# PhoneRobot.net
KiCad netlist of a schematic drawn in EAGLE
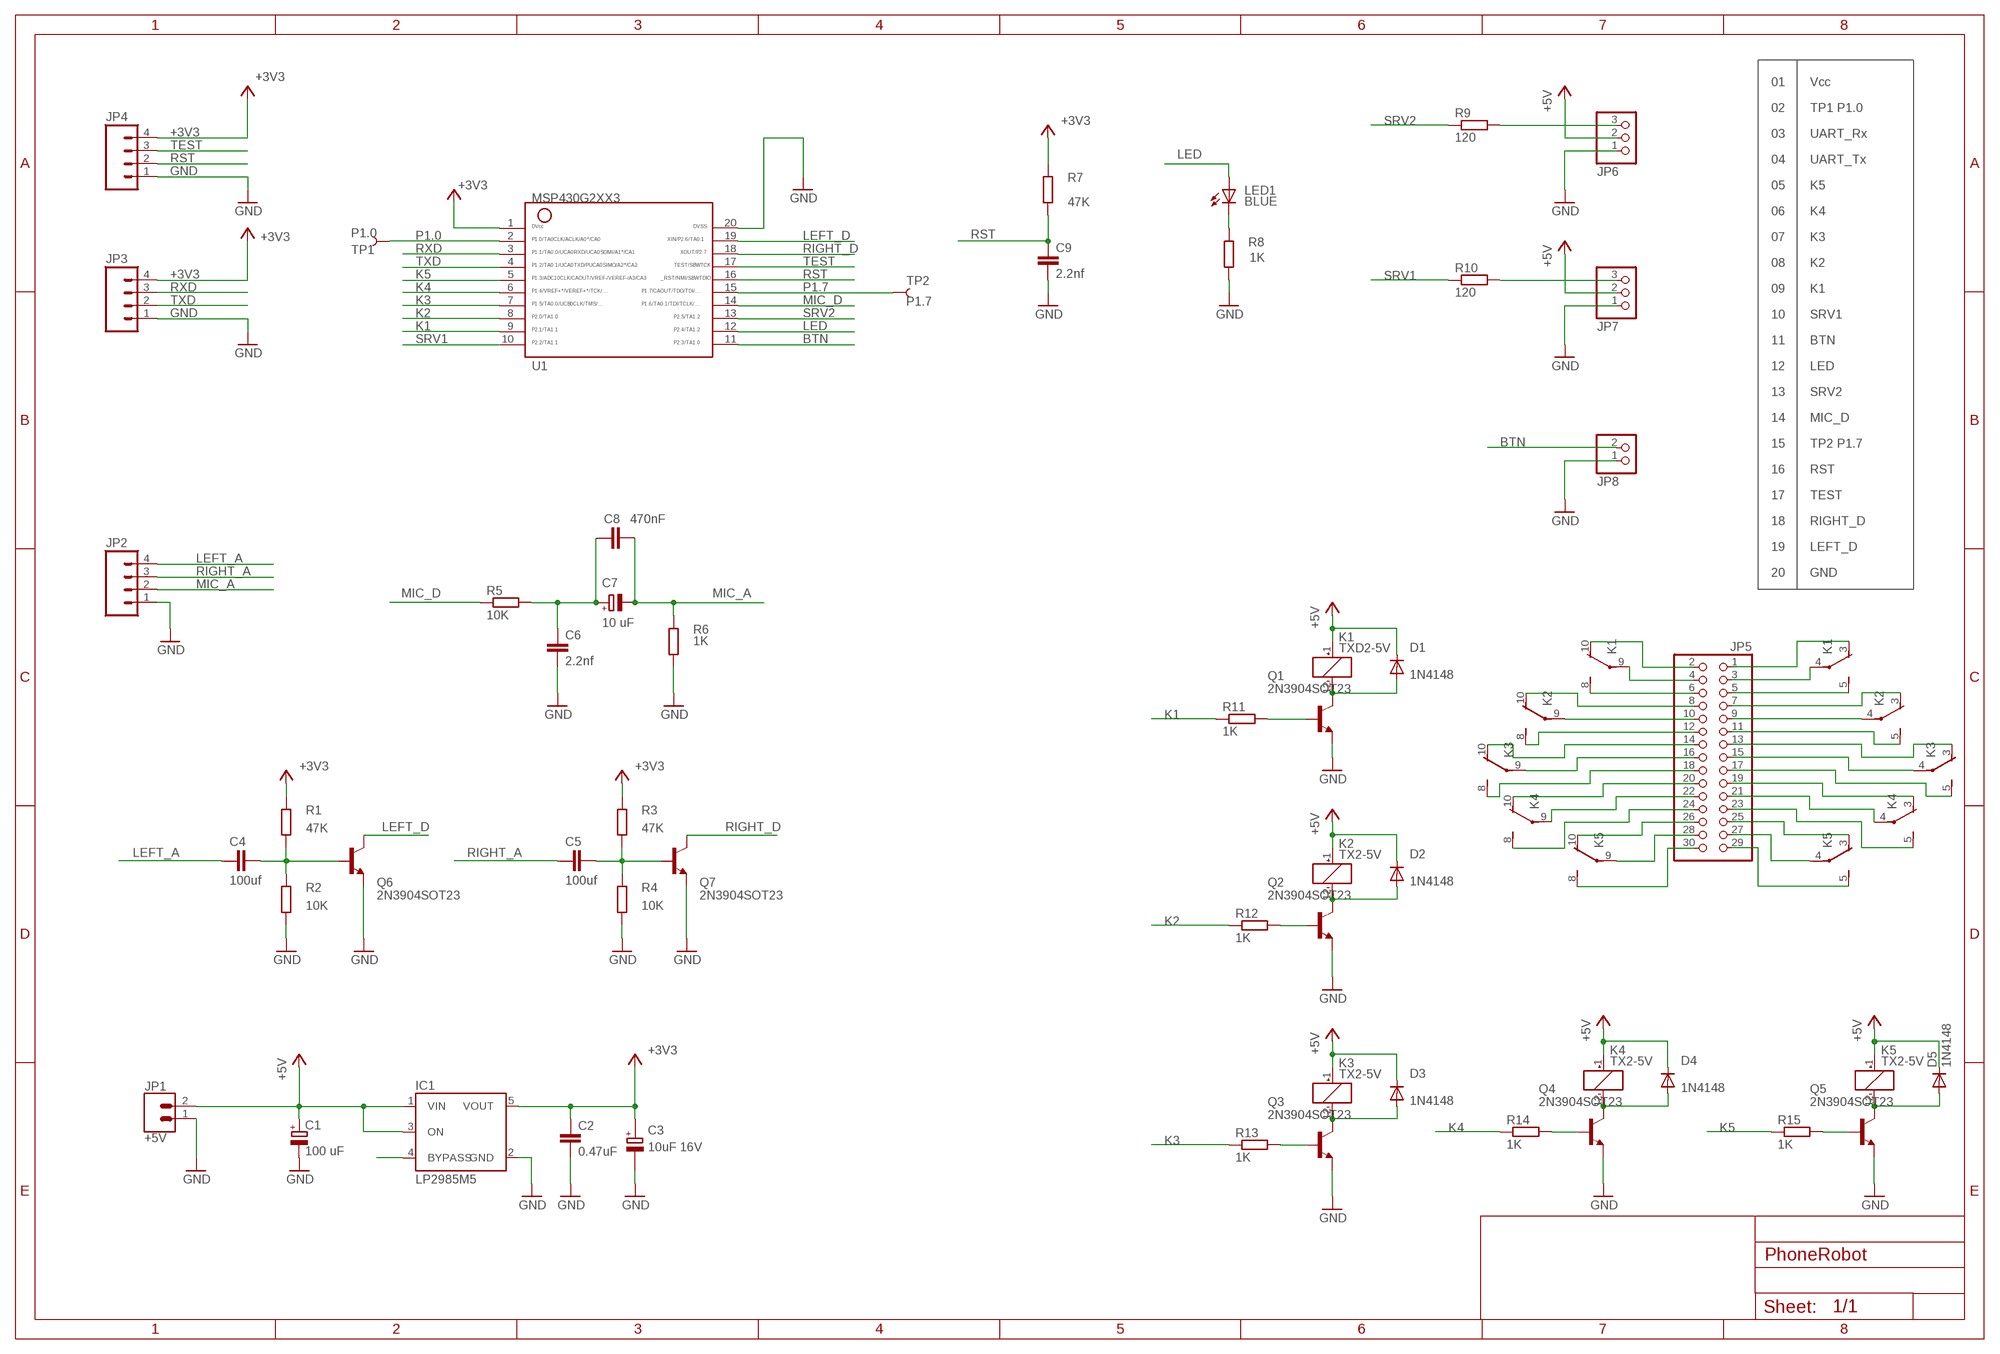
[diagram p0: schematic, sheet 1]

(export (version "E")
  (design (tool "Eeschema 10.0.6"))
  (components
    (comp (ref "C1")
      (value "100 uF")
      (footprint "eagle-import:E2,5-7")
      (libsource (lib "eagle-import") (part "CPOL-EUE2.5-7"))
    )
    (comp (ref "C2")
      (value "0.47uF")
      (footprint "eagle-import:C0805")
      (libsource (lib "eagle-import") (part "C-EUC0805"))
    )
    (comp (ref "C3")
      (value "10uF 16V")
      (footprint "eagle-import:CAPMP3216X180N")
      (libsource (lib "eagle-import") (part "POLARISED_A_CASE"))
    )
    (comp (ref "C4")
      (value "100uf")
      (footprint "eagle-import:C0805")
      (libsource (lib "eagle-import") (part "C-EUC0805"))
    )
    (comp (ref "C5")
      (value "100uf")
      (footprint "eagle-import:C0805")
      (libsource (lib "eagle-import") (part "C-EUC0805"))
    )
    (comp (ref "C6")
      (value "2.2nf")
      (footprint "eagle-import:C0805")
      (libsource (lib "eagle-import") (part "C-EUC0805"))
    )
    (comp (ref "C7")
      (value "10 uF")
      (footprint "eagle-import:E2,5-7")
      (libsource (lib "eagle-import") (part "CPOL-EUE2.5-7"))
    )
    (comp (ref "C8")
      (value "470nF")
      (footprint "eagle-import:C0805")
      (libsource (lib "eagle-import") (part "C-EUC0805"))
    )
    (comp (ref "C9")
      (value "2.2nf")
      (footprint "eagle-import:C0805")
      (libsource (lib "eagle-import") (part "C-EUC0805"))
    )
    (comp (ref "D1")
      (value "1N4148")
      (footprint "eagle-import:SOD123")
      (libsource (lib "eagle-import") (part "DIODE-SOD123"))
    )
    (comp (ref "D2")
      (value "1N4148")
      (footprint "eagle-import:SOD123")
      (libsource (lib "eagle-import") (part "DIODE-SOD123"))
    )
    (comp (ref "D3")
      (value "1N4148")
      (footprint "eagle-import:SOD123")
      (libsource (lib "eagle-import") (part "DIODE-SOD123"))
    )
    (comp (ref "D4")
      (value "1N4148")
      (footprint "eagle-import:SOD123")
      (libsource (lib "eagle-import") (part "DIODE-SOD123"))
    )
    (comp (ref "D5")
      (value "1N4148")
      (footprint "eagle-import:SOD123")
      (libsource (lib "eagle-import") (part "DIODE-SOD123"))
    )
    (comp (ref "IC1")
      (value "LP2985M5")
      (footprint "eagle-import:SOT23-5")
      (libsource (lib "eagle-import") (part "LP2985M5"))
    )
    (comp (ref "JP1")
      (value "+5V")
      (footprint "eagle-import:BLUE_TERM")
      (libsource (lib "eagle-import") (part "BLUE_TERM"))
    )
    (comp (ref "JP2")
      (value "M04PTH")
      (footprint "eagle-import:1X04")
      (libsource (lib "eagle-import") (part "M04PTH"))
    )
    (comp (ref "JP3")
      (value "M04PTH")
      (footprint "eagle-import:1X04")
      (libsource (lib "eagle-import") (part "M04PTH"))
    )
    (comp (ref "JP4")
      (value "M04PTH")
      (footprint "eagle-import:1X04")
      (libsource (lib "eagle-import") (part "M04PTH"))
    )
    (comp (ref "JP5")
      (value "PINHD-2X15")
      (footprint "eagle-import:2X15")
      (libsource (lib "eagle-import") (part "PINHD-2X15"))
    )
    (comp (ref "JP6")
      (value "PINHD-1X3")
      (footprint "eagle-import:1X03")
      (libsource (lib "eagle-import") (part "PINHD-1X3"))
    )
    (comp (ref "JP7")
      (value "PINHD-1X3")
      (footprint "eagle-import:1X03")
      (libsource (lib "eagle-import") (part "PINHD-1X3"))
    )
    (comp (ref "JP8")
      (value "PINHD-1X2")
      (footprint "eagle-import:1X02")
      (libsource (lib "eagle-import") (part "PINHD-1X2"))
    )
    (comp (ref "K1")
      (value "TXD2-5V")
      (footprint "eagle-import:TXD2")
      (libsource (lib "eagle-import") (part "TX?-D25V"))
    )
    (comp (ref "K2")
      (value "TX2-5V")
      (footprint "eagle-import:TX2")
      (fields (field (name "MF") "AROMAT/ MATSUSHITA"))
      (libsource (lib "eagle-import") (part "TX2?-5V"))
    )
    (comp (ref "K3")
      (value "TX2-5V")
      (footprint "eagle-import:TX2")
      (fields (field (name "MF") "AROMAT/ MATSUSHITA"))
      (libsource (lib "eagle-import") (part "TX2?-5V"))
    )
    (comp (ref "K4")
      (value "TX2-5V")
      (footprint "eagle-import:TX2")
      (fields (field (name "MF") "AROMAT/ MATSUSHITA"))
      (libsource (lib "eagle-import") (part "TX2?-5V"))
    )
    (comp (ref "K5")
      (value "TX2-5V")
      (footprint "eagle-import:TX2")
      (fields (field (name "MF") "AROMAT/ MATSUSHITA"))
      (libsource (lib "eagle-import") (part "TX2?-5V"))
    )
    (comp (ref "LED1")
      (value "BLUE")
      (footprint "eagle-import:CHIP-LED0805")
      (libsource (lib "eagle-import") (part "LEDCHIP-LED0805"))
    )
    (comp (ref "Q1")
      (value "2N3904SOT23")
      (footprint "eagle-import:SOT23-BEC")
      (libsource (lib "eagle-import") (part "2N3904SOT23"))
    )
    (comp (ref "Q2")
      (value "2N3904SOT23")
      (footprint "eagle-import:SOT23-BEC")
      (libsource (lib "eagle-import") (part "2N3904SOT23"))
    )
    (comp (ref "Q3")
      (value "2N3904SOT23")
      (footprint "eagle-import:SOT23-BEC")
      (libsource (lib "eagle-import") (part "2N3904SOT23"))
    )
    (comp (ref "Q4")
      (value "2N3904SOT23")
      (footprint "eagle-import:SOT23-BEC")
      (libsource (lib "eagle-import") (part "2N3904SOT23"))
    )
    (comp (ref "Q5")
      (value "2N3904SOT23")
      (footprint "eagle-import:SOT23-BEC")
      (libsource (lib "eagle-import") (part "2N3904SOT23"))
    )
    (comp (ref "Q6")
      (value "2N3904SOT23")
      (footprint "eagle-import:SOT23-BEC")
      (libsource (lib "eagle-import") (part "2N3904SOT23"))
    )
    (comp (ref "Q7")
      (value "2N3904SOT23")
      (footprint "eagle-import:SOT23-BEC")
      (libsource (lib "eagle-import") (part "2N3904SOT23"))
    )
    (comp (ref "R1")
      (value "47K")
      (footprint "eagle-import:R0805")
      (libsource (lib "eagle-import") (part "R-EU_R0805"))
    )
    (comp (ref "R2")
      (value "10K")
      (footprint "eagle-import:R0805")
      (libsource (lib "eagle-import") (part "R-EU_R0805"))
    )
    (comp (ref "R3")
      (value "47K")
      (footprint "eagle-import:R0805")
      (libsource (lib "eagle-import") (part "R-EU_R0805"))
    )
    (comp (ref "R4")
      (value "10K")
      (footprint "eagle-import:R0805")
      (libsource (lib "eagle-import") (part "R-EU_R0805"))
    )
    (comp (ref "R5")
      (value "10K")
      (footprint "eagle-import:R0805")
      (libsource (lib "eagle-import") (part "R-EU_R0805"))
    )
    (comp (ref "R6")
      (value "1K")
      (footprint "eagle-import:R0805")
      (libsource (lib "eagle-import") (part "R-EU_R0805"))
    )
    (comp (ref "R7")
      (value "47K")
      (footprint "eagle-import:R0805")
      (libsource (lib "eagle-import") (part "R-EU_R0805"))
    )
    (comp (ref "R8")
      (value "1K")
      (footprint "eagle-import:R0805")
      (libsource (lib "eagle-import") (part "R-EU_R0805"))
    )
    (comp (ref "R9")
      (value "120")
      (footprint "eagle-import:R0805")
      (libsource (lib "eagle-import") (part "R-EU_R0805"))
    )
    (comp (ref "R10")
      (value "120")
      (footprint "eagle-import:R0805")
      (libsource (lib "eagle-import") (part "R-EU_R0805"))
    )
    (comp (ref "R11")
      (value "1K")
      (footprint "eagle-import:R0805")
      (libsource (lib "eagle-import") (part "R-EU_R0805"))
    )
    (comp (ref "R12")
      (value "1K")
      (footprint "eagle-import:R0805")
      (libsource (lib "eagle-import") (part "R-EU_R0805"))
    )
    (comp (ref "R13")
      (value "1K")
      (footprint "eagle-import:R0805")
      (libsource (lib "eagle-import") (part "R-EU_R0805"))
    )
    (comp (ref "R14")
      (value "1K")
      (footprint "eagle-import:R0805")
      (libsource (lib "eagle-import") (part "R-EU_R0805"))
    )
    (comp (ref "R15")
      (value "1K")
      (footprint "eagle-import:R0805")
      (libsource (lib "eagle-import") (part "R-EU_R0805"))
    )
    (comp (ref "TP1")
      (value "P1.0")
      (footprint "eagle-import:PAD.03X.03")
      (libsource (lib "eagle-import") (part "TEST-POINT3"))
    )
    (comp (ref "TP2")
      (value "P1.7")
      (footprint "eagle-import:PAD.03X.03")
      (libsource (lib "eagle-import") (part "TEST-POINT3"))
    )
    (comp (ref "U1")
      (value "G2XX3---PW20")
      (footprint "eagle-import:PW20")
      (libsource (lib "eagle-import") (part "G2XX3---PW20"))
    )
  )
  (nets
    (net (code "1") (name "+3V3") (class "Default")
      (node (ref "C2") (pin "1") (pinfunction "1_1") (pintype "passive"))
      (node (ref "C3") (pin "+") (pinfunction "+_+") (pintype "passive"))
      (node (ref "IC1") (pin "5") (pinfunction "VOUT_5") (pintype "output"))
      (node (ref "JP3") (pin "4") (pinfunction "4_4") (pintype "passive"))
      (node (ref "JP4") (pin "4") (pinfunction "4_4") (pintype "passive"))
      (node (ref "R1") (pin "2") (pinfunction "2_2") (pintype "passive"))
      (node (ref "R3") (pin "2") (pinfunction "2_2") (pintype "passive"))
      (node (ref "R7") (pin "2") (pinfunction "2_2") (pintype "passive"))
      (node (ref "U1") (pin "1") (pinfunction "1_1") (pintype "bidirectional"))
    )
    (net (code "2") (name "+5V") (class "Default")
      (node (ref "C1") (pin "+") (pinfunction "+_+") (pintype "passive"))
      (node (ref "D1") (pin "C") (pinfunction "C_C") (pintype "passive"))
      (node (ref "D2") (pin "C") (pinfunction "C_C") (pintype "passive"))
      (node (ref "D3") (pin "C") (pinfunction "C_C") (pintype "passive"))
      (node (ref "D4") (pin "C") (pinfunction "C_C") (pintype "passive"))
      (node (ref "D5") (pin "C") (pinfunction "C_C") (pintype "passive"))
      (node (ref "IC1") (pin "1") (pinfunction "VIN_1") (pintype "power_in"))
      (node (ref "IC1") (pin "3") (pinfunction "ON_3") (pintype "input"))
      (node (ref "JP1") (pin "2") (pinfunction "2_2") (pintype "passive"))
      (node (ref "JP6") (pin "2") (pinfunction "2_2") (pintype "passive"))
      (node (ref "JP7") (pin "2") (pinfunction "2_2") (pintype "passive"))
      (node (ref "K1") (pin "1") (pinfunction "+_1") (pintype "passive"))
      (node (ref "K2") (pin "1") (pinfunction "+_1") (pintype "passive"))
      (node (ref "K3") (pin "1") (pinfunction "+_1") (pintype "passive"))
      (node (ref "K4") (pin "1") (pinfunction "+_1") (pintype "passive"))
      (node (ref "K5") (pin "1") (pinfunction "+_1") (pintype "passive"))
    )
    (net (code "3") (name "/BTN") (class "Default")
      (node (ref "JP8") (pin "2") (pinfunction "2_2") (pintype "passive"))
      (node (ref "U1") (pin "11") (pinfunction "11_11") (pintype "bidirectional"))
    )
    (net (code "4") (name "/K1") (class "Default")
      (node (ref "R11") (pin "1") (pinfunction "1_1") (pintype "passive"))
      (node (ref "U1") (pin "9") (pinfunction "9_9") (pintype "bidirectional"))
    )
    (net (code "5") (name "/K2") (class "Default")
      (node (ref "R12") (pin "1") (pinfunction "1_1") (pintype "passive"))
      (node (ref "U1") (pin "8") (pinfunction "8_8") (pintype "bidirectional"))
    )
    (net (code "6") (name "/K3") (class "Default")
      (node (ref "R13") (pin "1") (pinfunction "1_1") (pintype "passive"))
      (node (ref "U1") (pin "7") (pinfunction "7_7") (pintype "bidirectional"))
    )
    (net (code "7") (name "/K4") (class "Default")
      (node (ref "R14") (pin "1") (pinfunction "1_1") (pintype "passive"))
      (node (ref "U1") (pin "6") (pinfunction "6_6") (pintype "bidirectional"))
    )
    (net (code "8") (name "/K5") (class "Default")
      (node (ref "R15") (pin "1") (pinfunction "1_1") (pintype "passive"))
      (node (ref "U1") (pin "5") (pinfunction "5_5") (pintype "bidirectional"))
    )
    (net (code "9") (name "/LED") (class "Default")
      (node (ref "LED1") (pin "A") (pinfunction "A_A") (pintype "passive"))
      (node (ref "U1") (pin "12") (pinfunction "12_12") (pintype "bidirectional"))
    )
    (net (code "10") (name "/LEFT_A") (class "Default")
      (node (ref "C4") (pin "1") (pinfunction "1_1") (pintype "passive"))
      (node (ref "JP2") (pin "4") (pinfunction "4_4") (pintype "passive"))
    )
    (net (code "11") (name "/LEFT_D") (class "Default")
      (node (ref "Q6") (pin "C") (pinfunction "C_C") (pintype "passive"))
      (node (ref "U1") (pin "19") (pinfunction "19_19") (pintype "bidirectional"))
    )
    (net (code "12") (name "/MIC_A") (class "Default")
      (node (ref "C7") (pin "-") (pinfunction "-_-") (pintype "passive"))
      (node (ref "C8") (pin "2") (pinfunction "2_2") (pintype "passive"))
      (node (ref "JP2") (pin "2") (pinfunction "2_2") (pintype "passive"))
      (node (ref "R6") (pin "2") (pinfunction "2_2") (pintype "passive"))
    )
    (net (code "13") (name "/MIC_D") (class "Default")
      (node (ref "R5") (pin "1") (pinfunction "1_1") (pintype "passive"))
      (node (ref "U1") (pin "14") (pinfunction "14_14") (pintype "bidirectional"))
    )
    (net (code "14") (name "/P1.0") (class "Default")
      (node (ref "TP1") (pin "P$1") (pinfunction "1_P$1") (pintype "bidirectional"))
      (node (ref "U1") (pin "2") (pinfunction "2_2") (pintype "bidirectional"))
    )
    (net (code "15") (name "/P1.7") (class "Default")
      (node (ref "TP2") (pin "P$1") (pinfunction "1_P$1") (pintype "bidirectional"))
      (node (ref "U1") (pin "15") (pinfunction "15_15") (pintype "bidirectional"))
    )
    (net (code "16") (name "/RIGHT_A") (class "Default")
      (node (ref "C5") (pin "1") (pinfunction "1_1") (pintype "passive"))
      (node (ref "JP2") (pin "3") (pinfunction "3_3") (pintype "passive"))
    )
    (net (code "17") (name "/RIGHT_D") (class "Default")
      (node (ref "Q7") (pin "C") (pinfunction "C_C") (pintype "passive"))
      (node (ref "U1") (pin "18") (pinfunction "18_18") (pintype "bidirectional"))
    )
    (net (code "18") (name "/RST") (class "Default")
      (node (ref "C9") (pin "1") (pinfunction "1_1") (pintype "passive"))
      (node (ref "JP4") (pin "2") (pinfunction "2_2") (pintype "passive"))
      (node (ref "R7") (pin "1") (pinfunction "1_1") (pintype "passive"))
      (node (ref "U1") (pin "16") (pinfunction "16_16") (pintype "bidirectional"))
    )
    (net (code "19") (name "/RXD") (class "Default")
      (node (ref "JP3") (pin "3") (pinfunction "3_3") (pintype "passive"))
      (node (ref "U1") (pin "3") (pinfunction "3_3") (pintype "bidirectional"))
    )
    (net (code "20") (name "/SRV1") (class "Default")
      (node (ref "R10") (pin "1") (pinfunction "1_1") (pintype "passive"))
      (node (ref "U1") (pin "10") (pinfunction "10_10") (pintype "bidirectional"))
    )
    (net (code "21") (name "/SRV2") (class "Default")
      (node (ref "R9") (pin "1") (pinfunction "1_1") (pintype "passive"))
      (node (ref "U1") (pin "13") (pinfunction "13_13") (pintype "bidirectional"))
    )
    (net (code "22") (name "/TEST") (class "Default")
      (node (ref "JP4") (pin "3") (pinfunction "3_3") (pintype "passive"))
      (node (ref "U1") (pin "17") (pinfunction "17_17") (pintype "bidirectional"))
    )
    (net (code "23") (name "/TXD") (class "Default")
      (node (ref "JP3") (pin "2") (pinfunction "2_2") (pintype "passive"))
      (node (ref "U1") (pin "4") (pinfunction "4_4") (pintype "bidirectional"))
    )
    (net (code "24") (name "GND") (class "Default")
      (node (ref "C1") (pin "-") (pinfunction "-_-") (pintype "passive"))
      (node (ref "C2") (pin "2") (pinfunction "2_2") (pintype "passive"))
      (node (ref "C3") (pin "-") (pinfunction "-_-") (pintype "passive"))
      (node (ref "C6") (pin "2") (pinfunction "2_2") (pintype "passive"))
      (node (ref "C9") (pin "2") (pinfunction "2_2") (pintype "passive"))
      (node (ref "IC1") (pin "2") (pinfunction "GND_2") (pintype "power_in"))
      (node (ref "JP1") (pin "1") (pinfunction "1_1") (pintype "passive"))
      (node (ref "JP2") (pin "1") (pinfunction "1_1") (pintype "passive"))
      (node (ref "JP3") (pin "1") (pinfunction "1_1") (pintype "passive"))
      (node (ref "JP4") (pin "1") (pinfunction "1_1") (pintype "passive"))
      (node (ref "JP6") (pin "1") (pinfunction "1_1") (pintype "passive"))
      (node (ref "JP7") (pin "1") (pinfunction "1_1") (pintype "passive"))
      (node (ref "JP8") (pin "1") (pinfunction "1_1") (pintype "passive"))
      (node (ref "Q1") (pin "E") (pinfunction "E_E") (pintype "passive"))
      (node (ref "Q2") (pin "E") (pinfunction "E_E") (pintype "passive"))
      (node (ref "Q3") (pin "E") (pinfunction "E_E") (pintype "passive"))
      (node (ref "Q4") (pin "E") (pinfunction "E_E") (pintype "passive"))
      (node (ref "Q5") (pin "E") (pinfunction "E_E") (pintype "passive"))
      (node (ref "Q6") (pin "E") (pinfunction "E_E") (pintype "passive"))
      (node (ref "Q7") (pin "E") (pinfunction "E_E") (pintype "passive"))
      (node (ref "R2") (pin "1") (pinfunction "1_1") (pintype "passive"))
      (node (ref "R4") (pin "1") (pinfunction "1_1") (pintype "passive"))
      (node (ref "R6") (pin "1") (pinfunction "1_1") (pintype "passive"))
      (node (ref "R8") (pin "1") (pinfunction "1_1") (pintype "passive"))
      (node (ref "U1") (pin "20") (pinfunction "20_20") (pintype "bidirectional"))
    )
    (net (code "25") (name "Net-(C4-Pad2)") (class "Default")
      (node (ref "C4") (pin "2") (pinfunction "2_2") (pintype "passive"))
      (node (ref "Q6") (pin "B") (pinfunction "B_B") (pintype "passive"))
      (node (ref "R1") (pin "1") (pinfunction "1_1") (pintype "passive"))
      (node (ref "R2") (pin "2") (pinfunction "2_2") (pintype "passive"))
    )
    (net (code "26") (name "Net-(C5-Pad2)") (class "Default")
      (node (ref "C5") (pin "2") (pinfunction "2_2") (pintype "passive"))
      (node (ref "Q7") (pin "B") (pinfunction "B_B") (pintype "passive"))
      (node (ref "R3") (pin "1") (pinfunction "1_1") (pintype "passive"))
      (node (ref "R4") (pin "2") (pinfunction "2_2") (pintype "passive"))
    )
    (net (code "27") (name "Net-(C6-Pad1)") (class "Default")
      (node (ref "C6") (pin "1") (pinfunction "1_1") (pintype "passive"))
      (node (ref "C7") (pin "+") (pinfunction "+_+") (pintype "passive"))
      (node (ref "C8") (pin "1") (pinfunction "1_1") (pintype "passive"))
      (node (ref "R5") (pin "2") (pinfunction "2_2") (pintype "passive"))
    )
    (net (code "28") (name "Net-(JP6-Pad3)") (class "Default")
      (node (ref "JP6") (pin "3") (pinfunction "3_3") (pintype "passive"))
      (node (ref "R9") (pin "2") (pinfunction "2_2") (pintype "passive"))
    )
    (net (code "29") (name "Net-(JP7-Pad3)") (class "Default")
      (node (ref "JP7") (pin "3") (pinfunction "3_3") (pintype "passive"))
      (node (ref "R10") (pin "2") (pinfunction "2_2") (pintype "passive"))
    )
    (net (code "30") (name "Net-(K1A-O)") (class "Default")
      (node (ref "JP5") (pin "1") (pinfunction "1_1") (pintype "passive"))
      (node (ref "K1") (pin "3") (pinfunction "O_3") (pintype "passive"))
    )
    (net (code "31") (name "Net-(K1A-P)") (class "Default")
      (node (ref "JP5") (pin "3") (pinfunction "3_3") (pintype "passive"))
      (node (ref "K1") (pin "4") (pinfunction "P_4") (pintype "passive"))
    )
    (net (code "32") (name "Net-(K1A-S)") (class "Default")
      (node (ref "JP5") (pin "5") (pinfunction "5_5") (pintype "passive"))
      (node (ref "K1") (pin "5") (pinfunction "S_5") (pintype "passive"))
    )
    (net (code "33") (name "Net-(K1B-O)") (class "Default")
      (node (ref "JP5") (pin "2") (pinfunction "2_2") (pintype "passive"))
      (node (ref "K1") (pin "10") (pinfunction "O_10") (pintype "passive"))
    )
    (net (code "34") (name "Net-(K1B-P)") (class "Default")
      (node (ref "JP5") (pin "4") (pinfunction "4_4") (pintype "passive"))
      (node (ref "K1") (pin "9") (pinfunction "P_9") (pintype "passive"))
    )
    (net (code "35") (name "Net-(K1B-S)") (class "Default")
      (node (ref "JP5") (pin "6") (pinfunction "6_6") (pintype "passive"))
      (node (ref "K1") (pin "8") (pinfunction "S_8") (pintype "passive"))
    )
    (net (code "36") (name "Net-(K1C--)") (class "Default")
      (node (ref "D1") (pin "A") (pinfunction "A_A") (pintype "passive"))
      (node (ref "K1") (pin "12") (pinfunction "-_12") (pintype "passive"))
      (node (ref "Q1") (pin "C") (pinfunction "C_C") (pintype "passive"))
    )
    (net (code "37") (name "Net-(K2A-O)") (class "Default")
      (node (ref "JP5") (pin "7") (pinfunction "7_7") (pintype "passive"))
      (node (ref "K2") (pin "3") (pinfunction "O_3") (pintype "passive"))
    )
    (net (code "38") (name "Net-(K2A-P)") (class "Default")
      (node (ref "JP5") (pin "9") (pinfunction "9_9") (pintype "passive"))
      (node (ref "K2") (pin "4") (pinfunction "P_4") (pintype "passive"))
    )
    (net (code "39") (name "Net-(K2A-S)") (class "Default")
      (node (ref "JP5") (pin "11") (pinfunction "11_11") (pintype "passive"))
      (node (ref "K2") (pin "5") (pinfunction "S_5") (pintype "passive"))
    )
    (net (code "40") (name "Net-(K2B-O)") (class "Default")
      (node (ref "JP5") (pin "8") (pinfunction "8_8") (pintype "passive"))
      (node (ref "K2") (pin "10") (pinfunction "O_10") (pintype "passive"))
    )
    (net (code "41") (name "Net-(K2B-P)") (class "Default")
      (node (ref "JP5") (pin "10") (pinfunction "10_10") (pintype "passive"))
      (node (ref "K2") (pin "9") (pinfunction "P_9") (pintype "passive"))
    )
    (net (code "42") (name "Net-(K2B-S)") (class "Default")
      (node (ref "JP5") (pin "12") (pinfunction "12_12") (pintype "passive"))
      (node (ref "K2") (pin "8") (pinfunction "S_8") (pintype "passive"))
    )
    (net (code "43") (name "Net-(K2C--)") (class "Default")
      (node (ref "D2") (pin "A") (pinfunction "A_A") (pintype "passive"))
      (node (ref "K2") (pin "12") (pinfunction "-_12") (pintype "passive"))
      (node (ref "Q2") (pin "C") (pinfunction "C_C") (pintype "passive"))
    )
    (net (code "44") (name "Net-(K3A-O)") (class "Default")
      (node (ref "JP5") (pin "13") (pinfunction "13_13") (pintype "passive"))
      (node (ref "K3") (pin "3") (pinfunction "O_3") (pintype "passive"))
    )
    (net (code "45") (name "Net-(K3A-P)") (class "Default")
      (node (ref "JP5") (pin "15") (pinfunction "15_15") (pintype "passive"))
      (node (ref "K3") (pin "4") (pinfunction "P_4") (pintype "passive"))
    )
    (net (code "46") (name "Net-(K3A-S)") (class "Default")
      (node (ref "JP5") (pin "17") (pinfunction "17_17") (pintype "passive"))
      (node (ref "K3") (pin "5") (pinfunction "S_5") (pintype "passive"))
    )
    (net (code "47") (name "Net-(K3B-O)") (class "Default")
      (node (ref "JP5") (pin "14") (pinfunction "14_14") (pintype "passive"))
      (node (ref "K3") (pin "10") (pinfunction "O_10") (pintype "passive"))
    )
    (net (code "48") (name "Net-(K3B-P)") (class "Default")
      (node (ref "JP5") (pin "16") (pinfunction "16_16") (pintype "passive"))
      (node (ref "K3") (pin "9") (pinfunction "P_9") (pintype "passive"))
    )
    (net (code "49") (name "Net-(K3B-S)") (class "Default")
      (node (ref "JP5") (pin "18") (pinfunction "18_18") (pintype "passive"))
      (node (ref "K3") (pin "8") (pinfunction "S_8") (pintype "passive"))
    )
    (net (code "50") (name "Net-(K3C--)") (class "Default")
      (node (ref "D3") (pin "A") (pinfunction "A_A") (pintype "passive"))
      (node (ref "K3") (pin "12") (pinfunction "-_12") (pintype "passive"))
      (node (ref "Q3") (pin "C") (pinfunction "C_C") (pintype "passive"))
    )
    (net (code "51") (name "Net-(K4A-O)") (class "Default")
      (node (ref "JP5") (pin "19") (pinfunction "19_19") (pintype "passive"))
      (node (ref "K4") (pin "3") (pinfunction "O_3") (pintype "passive"))
    )
    (net (code "52") (name "Net-(K4A-P)") (class "Default")
      (node (ref "JP5") (pin "21") (pinfunction "21_21") (pintype "passive"))
      (node (ref "K4") (pin "4") (pinfunction "P_4") (pintype "passive"))
    )
    (net (code "53") (name "Net-(K4A-S)") (class "Default")
      (node (ref "JP5") (pin "23") (pinfunction "23_23") (pintype "passive"))
      (node (ref "K4") (pin "5") (pinfunction "S_5") (pintype "passive"))
    )
    (net (code "54") (name "Net-(K4B-O)") (class "Default")
      (node (ref "JP5") (pin "20") (pinfunction "20_20") (pintype "passive"))
      (node (ref "K4") (pin "10") (pinfunction "O_10") (pintype "passive"))
    )
    (net (code "55") (name "Net-(K4B-P)") (class "Default")
      (node (ref "JP5") (pin "22") (pinfunction "22_22") (pintype "passive"))
      (node (ref "K4") (pin "9") (pinfunction "P_9") (pintype "passive"))
    )
    (net (code "56") (name "Net-(K4B-S)") (class "Default")
      (node (ref "JP5") (pin "24") (pinfunction "24_24") (pintype "passive"))
      (node (ref "K4") (pin "8") (pinfunction "S_8") (pintype "passive"))
    )
    (net (code "57") (name "Net-(K4C--)") (class "Default")
      (node (ref "D4") (pin "A") (pinfunction "A_A") (pintype "passive"))
      (node (ref "K4") (pin "12") (pinfunction "-_12") (pintype "passive"))
      (node (ref "Q4") (pin "C") (pinfunction "C_C") (pintype "passive"))
    )
    (net (code "58") (name "Net-(K5A-O)") (class "Default")
      (node (ref "JP5") (pin "25") (pinfunction "25_25") (pintype "passive"))
      (node (ref "K5") (pin "3") (pinfunction "O_3") (pintype "passive"))
    )
    (net (code "59") (name "Net-(K5A-P)") (class "Default")
      (node (ref "JP5") (pin "27") (pinfunction "27_27") (pintype "passive"))
      (node (ref "K5") (pin "4") (pinfunction "P_4") (pintype "passive"))
    )
    (net (code "60") (name "Net-(K5A-S)") (class "Default")
      (node (ref "JP5") (pin "29") (pinfunction "29_29") (pintype "passive"))
      (node (ref "K5") (pin "5") (pinfunction "S_5") (pintype "passive"))
    )
    (net (code "61") (name "Net-(K5B-O)") (class "Default")
      (node (ref "JP5") (pin "26") (pinfunction "26_26") (pintype "passive"))
      (node (ref "K5") (pin "10") (pinfunction "O_10") (pintype "passive"))
    )
    (net (code "62") (name "Net-(K5B-P)") (class "Default")
      (node (ref "JP5") (pin "28") (pinfunction "28_28") (pintype "passive"))
      (node (ref "K5") (pin "9") (pinfunction "P_9") (pintype "passive"))
    )
    (net (code "63") (name "Net-(K5B-S)") (class "Default")
      (node (ref "JP5") (pin "30") (pinfunction "30_30") (pintype "passive"))
      (node (ref "K5") (pin "8") (pinfunction "S_8") (pintype "passive"))
    )
    (net (code "64") (name "Net-(K5C--)") (class "Default")
      (node (ref "D5") (pin "A") (pinfunction "A_A") (pintype "passive"))
      (node (ref "K5") (pin "12") (pinfunction "-_12") (pintype "passive"))
      (node (ref "Q5") (pin "C") (pinfunction "C_C") (pintype "passive"))
    )
    (net (code "65") (name "Net-(LED1-PadC)") (class "Default")
      (node (ref "LED1") (pin "C") (pinfunction "C_C") (pintype "passive"))
      (node (ref "R8") (pin "2") (pinfunction "2_2") (pintype "passive"))
    )
    (net (code "66") (name "Net-(Q1-PadB)") (class "Default")
      (node (ref "Q1") (pin "B") (pinfunction "B_B") (pintype "passive"))
      (node (ref "R11") (pin "2") (pinfunction "2_2") (pintype "passive"))
    )
    (net (code "67") (name "Net-(Q2-PadB)") (class "Default")
      (node (ref "Q2") (pin "B") (pinfunction "B_B") (pintype "passive"))
      (node (ref "R12") (pin "2") (pinfunction "2_2") (pintype "passive"))
    )
    (net (code "68") (name "Net-(Q3-PadB)") (class "Default")
      (node (ref "Q3") (pin "B") (pinfunction "B_B") (pintype "passive"))
      (node (ref "R13") (pin "2") (pinfunction "2_2") (pintype "passive"))
    )
    (net (code "69") (name "Net-(Q4-PadB)") (class "Default")
      (node (ref "Q4") (pin "B") (pinfunction "B_B") (pintype "passive"))
      (node (ref "R14") (pin "2") (pinfunction "2_2") (pintype "passive"))
    )
    (net (code "70") (name "Net-(Q5-PadB)") (class "Default")
      (node (ref "Q5") (pin "B") (pinfunction "B_B") (pintype "passive"))
      (node (ref "R15") (pin "2") (pinfunction "2_2") (pintype "passive"))
    )
    (net (code "71") (name "unconnected-(IC1-BYPASS-Pad4)") (class "Default")
      (node (ref "IC1") (pin "4") (pinfunction "BYPASS_4") (pintype "passive"))
    )
  )
)
